# Ethernet_ACS_Toggle.net
KiCad netlist of a schematic drawn in EasyEDA Pro
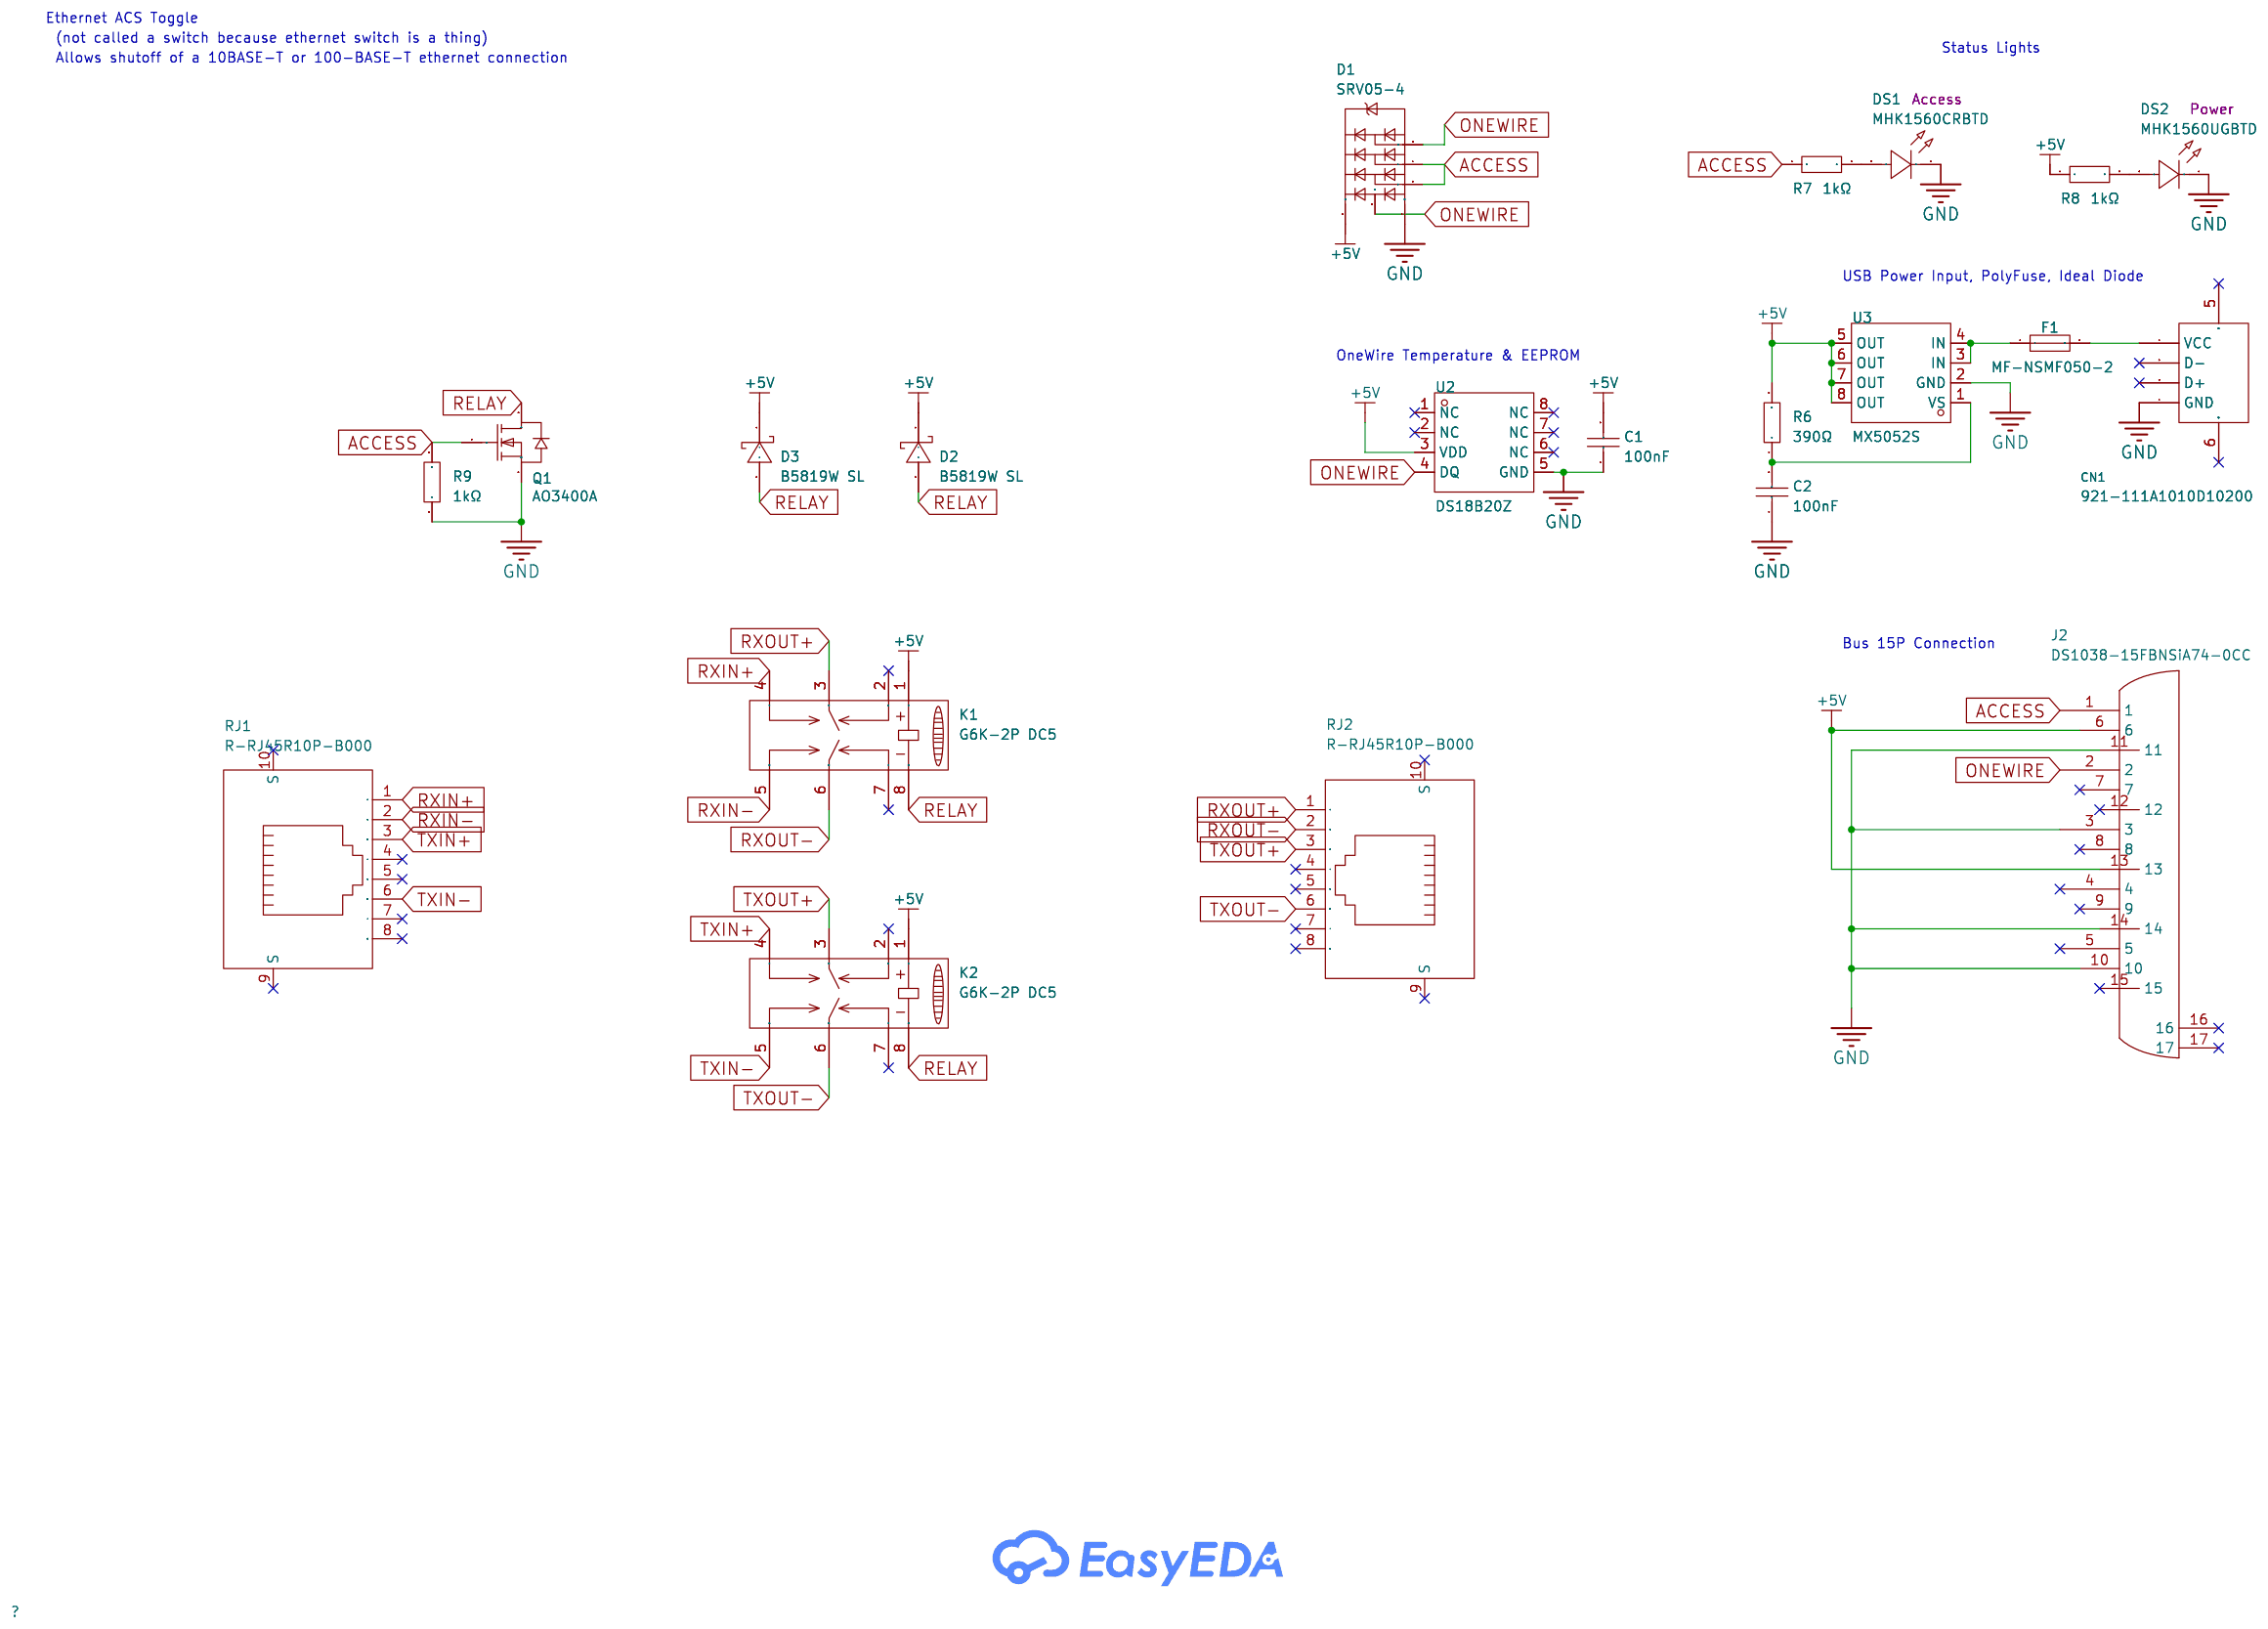
[diagram p0: schematic sheet]

(export (version "E")
  (design (tool "Eeschema 10.0.6"))
  (components
    (comp (ref "C1")
      (value "100nF")
      (footprint "easyedapro:C0805")
      (description "Capacitance:100nF Tolerance:±10% Tolerance:±10% Voltage Rating:100V Temperature Coefficient:X7R")
      (fields
        (field (name "Manufacturer Part") "CL21B104KCFNNNE")
        (field (name "Manufacturer") "SAMSUNG(三星)")
      )
      (libsource (lib "easyedapro") (part "CL21B104KCFNNNE"))
    )
    (comp (ref "C2")
      (value "100nF")
      (footprint "easyedapro:C0805")
      (description "Capacitance:100nF Tolerance:±10% Tolerance:±10% Voltage Rating:100V Temperature Coefficient:X7R")
      (fields
        (field (name "Manufacturer Part") "CL21B104KCFNNNE")
        (field (name "Manufacturer") "SAMSUNG(三星)")
      )
      (libsource (lib "easyedapro") (part "CL21B104KCFNNNE"))
    )
    (comp (ref "CN1")
      (value "921-111A1010D10200")
      (footprint "easyedapro:USB-B_TH_USB-B-FEMALE-90")
      (fields (field (name "Manufacturer") "精拓金"))
      (libsource (lib "easyedapro") (part "USB-B-Female-90"))
    )
    (comp (ref "D1")
      (value "SRV05-4")
      (footprint "easyedapro:SOT-23-6_L2.9-W1.6-P0.95-LS2.8-BL-1")
      (fields (field (name "Manufacturer") "R+O(宏嘉诚)"))
      (libsource (lib "easyedapro") (part "SRV05-4_C7420376"))
    )
    (comp (ref "D2")
      (value "B5819W SL")
      (footprint "easyedapro:SOD-123_L2.7-W1.6-LS3.7-RD-1")
      (fields (field (name "Manufacturer") "CJ(江苏长电/长晶)"))
      (libsource (lib "easyedapro") (part "B5819W_C8598"))
    )
    (comp (ref "D3")
      (value "B5819W SL")
      (footprint "easyedapro:SOD-123_L2.7-W1.6-LS3.7-RD-1")
      (fields (field (name "Manufacturer") "CJ(江苏长电/长晶)"))
      (libsource (lib "easyedapro") (part "B5819W_C8598"))
    )
    (comp (ref "DS1")
      (value "MHK1560CRBTD")
      (footprint "easyedapro:LED-TH_MHK1560UGBTD")
      (fields (field (name "Manufacturer") "MEIHUA(美华)") (field (name "Note") "Access"))
      (libsource (lib "easyedapro") (part "MHK1560CGBTD"))
    )
    (comp (ref "DS2")
      (value "MHK1560UGBTD")
      (footprint "easyedapro:LED-TH_MHK1560UGBTD")
      (fields (field (name "Manufacturer") "MEIHUA(美华)") (field (name "Note") "Power"))
      (libsource (lib "easyedapro") (part "MHK1560UGBTD"))
    )
    (comp (ref "F1")
      (value "MF-NSMF050-2")
      (footprint "easyedapro:F1206")
      (fields (field (name "Manufacturer") "BOURNS"))
      (libsource (lib "easyedapro") (part "MF-NSMF050-2"))
    )
    (comp (ref "J2")
      (value "DS1038-15FBNSiA74-0CC")
      (footprint "easyedapro:DSUB-TH_DS1038-15FBNSIA74-0CC")
      (fields (field (name "Manufacturer") "CONNFLY"))
      (libsource (lib "easyedapro") (part "DS1038-15FBNSIA74-0CC"))
    )
    (comp (ref "K1")
      (value "G6K-2P DC5")
      (footprint "easyedapro:RELAY-TH_G6K-2P")
      (fields (field (name "Manufacturer") "OMRON(欧姆龙)"))
      (libsource (lib "easyedapro") (part "G6K-2P DC5"))
    )
    (comp (ref "K2")
      (value "G6K-2P DC5")
      (footprint "easyedapro:RELAY-TH_G6K-2P")
      (fields (field (name "Manufacturer") "OMRON(欧姆龙)"))
      (libsource (lib "easyedapro") (part "G6K-2P DC5"))
    )
    (comp (ref "Q1")
      (value "AO3400A")
      (footprint "easyedapro:SOT-23-3_L2.9-W1.3-P1.90-LS2.4-BR")
      (fields (field (name "Manufacturer") "AOS"))
      (libsource (lib "easyedapro") (part "AO3400A"))
    )
    (comp (ref "R6")
      (value "390Ω")
      (footprint "easyedapro:R0805")
      (fields
        (field (name "Manufacturer Part") "0805W8F3900T5E")
        (field (name "Manufacturer") "UNI-ROYAL(厚声)")
      )
      (libsource (lib "easyedapro") (part "0805W8F3900T5E"))
    )
    (comp (ref "R7")
      (value "1kΩ")
      (footprint "easyedapro:R0805")
      (fields
        (field (name "Manufacturer Part") "0805W8F1001T5E")
        (field (name "Manufacturer") "UNI-ROYAL(厚声)")
      )
      (libsource (lib "easyedapro") (part "0805W8F1001T5E"))
    )
    (comp (ref "R8")
      (value "1kΩ")
      (footprint "easyedapro:R0805")
      (fields
        (field (name "Manufacturer Part") "0805W8F1001T5E")
        (field (name "Manufacturer") "UNI-ROYAL(厚声)")
      )
      (libsource (lib "easyedapro") (part "0805W8F1001T5E"))
    )
    (comp (ref "R9")
      (value "1kΩ")
      (footprint "easyedapro:R0805")
      (fields
        (field (name "Manufacturer Part") "0805W8F1001T5E")
        (field (name "Manufacturer") "UNI-ROYAL(厚声)")
      )
      (libsource (lib "easyedapro") (part "0805W8F1001T5E"))
    )
    (comp (ref "RJ1")
      (value "R-RJ45R10P-B000")
      (footprint "easyedapro:RJ45-TH_R-RJ45R10P-B000")
      (fields (field (name "Manufacturer") "Ckmtw(灿科盟)"))
      (libsource (lib "easyedapro") (part "R-RJ45R10P-B000"))
    )
    (comp (ref "RJ2")
      (value "R-RJ45R10P-B000")
      (footprint "easyedapro:RJ45-TH_R-RJ45R10P-B000")
      (fields (field (name "Manufacturer") "Ckmtw(灿科盟)"))
      (libsource (lib "easyedapro") (part "R-RJ45R10P-B000"))
    )
    (comp (ref "U2")
      (value "DS18B20Z")
      (footprint "easyedapro:SOP-8_L4.9-W3.9-P1.27-LS6.0-BL")
      (description "Resolution:±0.4°C Resolution:±0.4°C Supply Voltage:2.5V~5.5V Supply Voltage:2.5V~5.5V")
      (fields (field (name "Manufacturer") "UMW(友台半导体)"))
      (libsource (lib "easyedapro") (part "DS18B20Z"))
    )
    (comp (ref "U3")
      (value "MX5052S")
      (footprint "easyedapro:SOP-8_L4.9-W3.9-P1.27-LS6.0-BL")
      (fields (field (name "Manufacturer") "Wuxi Maxinmicro(无锡明芯微)"))
      (libsource (lib "easyedapro") (part "MX5052S"))
    )
  )
  (nets
    (net (code "1") (name "+5V") (class "Default")
      (node (ref "C1") (pin "2") (pinfunction "2_2") (pintype "input"))
      (node (ref "D1") (pin "5") (pinfunction "5_5") (pintype "unspecified"))
      (node (ref "D2") (pin "1") (pinfunction "-_1") (pintype "unspecified"))
      (node (ref "D3") (pin "1") (pinfunction "-_1") (pintype "unspecified"))
      (node (ref "J2") (pin "13") (pinfunction "13_13") (pintype "unspecified"))
      (node (ref "J2") (pin "6") (pinfunction "6_6") (pintype "unspecified"))
      (node (ref "K1") (pin "1") (pinfunction "1_1") (pintype "unspecified"))
      (node (ref "K2") (pin "1") (pinfunction "1_1") (pintype "unspecified"))
      (node (ref "R6") (pin "2") (pinfunction "2_2") (pintype "input"))
      (node (ref "R8") (pin "1") (pinfunction "1_1") (pintype "input"))
      (node (ref "U2") (pin "3") (pinfunction "VDD_3") (pintype "unspecified"))
      (node (ref "U3") (pin "5") (pinfunction "OUT_5") (pintype "unspecified"))
      (node (ref "U3") (pin "6") (pinfunction "OUT_6") (pintype "unspecified"))
      (node (ref "U3") (pin "7") (pinfunction "OUT_7") (pintype "unspecified"))
      (node (ref "U3") (pin "8") (pinfunction "OUT_8") (pintype "unspecified"))
    )
    (net (code "2") (name "ACCESS") (class "Default")
      (node (ref "D1") (pin "3") (pinfunction "3_3") (pintype "unspecified"))
      (node (ref "D1") (pin "4") (pinfunction "4_4") (pintype "unspecified"))
      (node (ref "J2") (pin "1") (pinfunction "1_1") (pintype "unspecified"))
      (node (ref "Q1") (pin "1") (pinfunction "G_1") (pintype "unspecified"))
      (node (ref "R7") (pin "1") (pinfunction "1_1") (pintype "input"))
      (node (ref "R9") (pin "2") (pinfunction "2_2") (pintype "input"))
    )
    (net (code "3") (name "GND") (class "Default")
      (node (ref "C1") (pin "1") (pinfunction "1_1") (pintype "input"))
      (node (ref "C2") (pin "1") (pinfunction "1_1") (pintype "input"))
      (node (ref "CN1") (pin "4") (pinfunction "GND_4") (pintype "input"))
      (node (ref "D1") (pin "2") (pinfunction "2_2") (pintype "unspecified"))
      (node (ref "DS1") (pin "1") (pinfunction "K_1") (pintype "unspecified"))
      (node (ref "DS2") (pin "1") (pinfunction "K_1") (pintype "unspecified"))
      (node (ref "J2") (pin "10") (pinfunction "10_10") (pintype "unspecified"))
      (node (ref "J2") (pin "11") (pinfunction "11_11") (pintype "unspecified"))
      (node (ref "J2") (pin "14") (pinfunction "14_14") (pintype "unspecified"))
      (node (ref "J2") (pin "3") (pinfunction "3_3") (pintype "unspecified"))
      (node (ref "Q1") (pin "2") (pinfunction "S_2") (pintype "unspecified"))
      (node (ref "R9") (pin "1") (pinfunction "1_1") (pintype "input"))
      (node (ref "U2") (pin "5") (pinfunction "GND_5") (pintype "unspecified"))
      (node (ref "U3") (pin "2") (pinfunction "GND_2") (pintype "unspecified"))
    )
    (net (code "4") (name "Net-(CN1-VCC)") (class "Default")
      (node (ref "CN1") (pin "1") (pinfunction "VCC_1") (pintype "input"))
      (node (ref "F1") (pin "2") (pinfunction "2_2") (pintype "unspecified"))
    )
    (net (code "5") (name "Net-(DS1-A)") (class "Default")
      (node (ref "DS1") (pin "2") (pinfunction "A_2") (pintype "unspecified"))
      (node (ref "R7") (pin "2") (pinfunction "2_2") (pintype "input"))
    )
    (net (code "6") (name "Net-(DS2-A)") (class "Default")
      (node (ref "DS2") (pin "2") (pinfunction "A_2") (pintype "unspecified"))
      (node (ref "R8") (pin "2") (pinfunction "2_2") (pintype "input"))
    )
    (net (code "7") (name "Net-(F1-Pad1)") (class "Default")
      (node (ref "F1") (pin "1") (pinfunction "1_1") (pintype "unspecified"))
      (node (ref "U3") (pin "3") (pinfunction "IN_3") (pintype "unspecified"))
      (node (ref "U3") (pin "4") (pinfunction "IN_4") (pintype "unspecified"))
    )
    (net (code "8") (name "Net-(U3-VS)") (class "Default")
      (node (ref "C2") (pin "2") (pinfunction "2_2") (pintype "input"))
      (node (ref "R6") (pin "1") (pinfunction "1_1") (pintype "input"))
      (node (ref "U3") (pin "1") (pinfunction "VS_1") (pintype "unspecified"))
    )
    (net (code "9") (name "ONEWIRE") (class "Default")
      (node (ref "D1") (pin "1") (pinfunction "1_1") (pintype "unspecified"))
      (node (ref "D1") (pin "6") (pinfunction "6_6") (pintype "unspecified"))
      (node (ref "J2") (pin "2") (pinfunction "2_2") (pintype "unspecified"))
      (node (ref "U2") (pin "4") (pinfunction "DQ_4") (pintype "unspecified"))
    )
    (net (code "10") (name "RELAY") (class "Default")
      (node (ref "D2") (pin "2") (pinfunction "+_2") (pintype "unspecified"))
      (node (ref "D3") (pin "2") (pinfunction "+_2") (pintype "unspecified"))
      (node (ref "K1") (pin "8") (pinfunction "8_8") (pintype "unspecified"))
      (node (ref "K2") (pin "8") (pinfunction "8_8") (pintype "unspecified"))
      (node (ref "Q1") (pin "3") (pinfunction "D_3") (pintype "unspecified"))
    )
    (net (code "11") (name "RXIN+") (class "Default")
      (node (ref "K1") (pin "4") (pinfunction "4_4") (pintype "unspecified"))
      (node (ref "RJ1") (pin "1") (pinfunction "1_1") (pintype "unspecified"))
    )
    (net (code "12") (name "RXIN-") (class "Default")
      (node (ref "K1") (pin "5") (pinfunction "5_5") (pintype "unspecified"))
      (node (ref "RJ1") (pin "2") (pinfunction "2_2") (pintype "unspecified"))
    )
    (net (code "13") (name "RXOUT+") (class "Default")
      (node (ref "K1") (pin "3") (pinfunction "3_3") (pintype "unspecified"))
      (node (ref "RJ2") (pin "1") (pinfunction "1_1") (pintype "unspecified"))
    )
    (net (code "14") (name "RXOUT-") (class "Default")
      (node (ref "K1") (pin "6") (pinfunction "6_6") (pintype "unspecified"))
      (node (ref "RJ2") (pin "2") (pinfunction "2_2") (pintype "unspecified"))
    )
    (net (code "15") (name "TXIN+") (class "Default")
      (node (ref "K2") (pin "4") (pinfunction "4_4") (pintype "unspecified"))
      (node (ref "RJ1") (pin "3") (pinfunction "3_3") (pintype "unspecified"))
    )
    (net (code "16") (name "TXIN-") (class "Default")
      (node (ref "K2") (pin "5") (pinfunction "5_5") (pintype "unspecified"))
      (node (ref "RJ1") (pin "6") (pinfunction "6_6") (pintype "unspecified"))
    )
    (net (code "17") (name "TXOUT+") (class "Default")
      (node (ref "K2") (pin "3") (pinfunction "3_3") (pintype "unspecified"))
      (node (ref "RJ2") (pin "3") (pinfunction "3_3") (pintype "unspecified"))
    )
    (net (code "18") (name "TXOUT-") (class "Default")
      (node (ref "K2") (pin "6") (pinfunction "6_6") (pintype "unspecified"))
      (node (ref "RJ2") (pin "6") (pinfunction "6_6") (pintype "unspecified"))
    )
    (net (code "19") (name "unconnected-(CN1-D+-Pad3)") (class "Default")
      (node (ref "CN1") (pin "3") (pinfunction "D+_3") (pintype "input+no_connect"))
    )
    (net (code "20") (name "unconnected-(CN1-D--Pad2)") (class "Default")
      (node (ref "CN1") (pin "2") (pinfunction "D-_2") (pintype "input+no_connect"))
    )
    (net (code "21") (name "unconnected-(CN1-SH1-Pad5)") (class "Default")
      (node (ref "CN1") (pin "5") (pinfunction "SH1_5") (pintype "input+no_connect"))
    )
    (net (code "22") (name "unconnected-(CN1-SH2-Pad6)") (class "Default")
      (node (ref "CN1") (pin "6") (pinfunction "SH2_6") (pintype "input+no_connect"))
    )
    (net (code "23") (name "unconnected-(J2-Pad4)") (class "Default")
      (node (ref "J2") (pin "4") (pinfunction "4_4") (pintype "unspecified+no_connect"))
    )
    (net (code "24") (name "unconnected-(J2-Pad5)") (class "Default")
      (node (ref "J2") (pin "5") (pinfunction "5_5") (pintype "unspecified+no_connect"))
    )
    (net (code "25") (name "unconnected-(J2-Pad7)") (class "Default")
      (node (ref "J2") (pin "7") (pinfunction "7_7") (pintype "unspecified+no_connect"))
    )
    (net (code "26") (name "unconnected-(J2-Pad8)") (class "Default")
      (node (ref "J2") (pin "8") (pinfunction "8_8") (pintype "unspecified+no_connect"))
    )
    (net (code "27") (name "unconnected-(J2-Pad9)") (class "Default")
      (node (ref "J2") (pin "9") (pinfunction "9_9") (pintype "unspecified+no_connect"))
    )
    (net (code "28") (name "unconnected-(J2-Pad12)") (class "Default")
      (node (ref "J2") (pin "12") (pinfunction "12_12") (pintype "unspecified+no_connect"))
    )
    (net (code "29") (name "unconnected-(J2-Pad15)") (class "Default")
      (node (ref "J2") (pin "15") (pinfunction "15_15") (pintype "unspecified+no_connect"))
    )
    (net (code "30") (name "unconnected-(J2-Pad16)") (class "Default")
      (node (ref "J2") (pin "16") (pinfunction "16_16") (pintype "unspecified+no_connect"))
    )
    (net (code "31") (name "unconnected-(J2-Pad17)") (class "Default")
      (node (ref "J2") (pin "17") (pinfunction "17_17") (pintype "unspecified+no_connect"))
    )
    (net (code "32") (name "unconnected-(K1-Pad2)") (class "Default")
      (node (ref "K1") (pin "2") (pinfunction "2_2") (pintype "unspecified+no_connect"))
    )
    (net (code "33") (name "unconnected-(K1-Pad7)") (class "Default")
      (node (ref "K1") (pin "7") (pinfunction "7_7") (pintype "unspecified+no_connect"))
    )
    (net (code "34") (name "unconnected-(K2-Pad2)") (class "Default")
      (node (ref "K2") (pin "2") (pinfunction "2_2") (pintype "unspecified+no_connect"))
    )
    (net (code "35") (name "unconnected-(K2-Pad7)") (class "Default")
      (node (ref "K2") (pin "7") (pinfunction "7_7") (pintype "unspecified+no_connect"))
    )
    (net (code "36") (name "unconnected-(RJ1-Pad4)") (class "Default")
      (node (ref "RJ1") (pin "4") (pinfunction "4_4") (pintype "unspecified+no_connect"))
    )
    (net (code "37") (name "unconnected-(RJ1-Pad5)") (class "Default")
      (node (ref "RJ1") (pin "5") (pinfunction "5_5") (pintype "unspecified+no_connect"))
    )
    (net (code "38") (name "unconnected-(RJ1-Pad7)") (class "Default")
      (node (ref "RJ1") (pin "7") (pinfunction "7_7") (pintype "unspecified+no_connect"))
    )
    (net (code "39") (name "unconnected-(RJ1-Pad8)") (class "Default")
      (node (ref "RJ1") (pin "8") (pinfunction "8_8") (pintype "unspecified+no_connect"))
    )
    (net (code "40") (name "unconnected-(RJ1-S-Pad9)") (class "Default")
      (node (ref "RJ1") (pin "9") (pinfunction "S_9") (pintype "unspecified+no_connect"))
    )
    (net (code "41") (name "unconnected-(RJ1-S-Pad10)") (class "Default")
      (node (ref "RJ1") (pin "10") (pinfunction "S_10") (pintype "unspecified+no_connect"))
    )
    (net (code "42") (name "unconnected-(RJ2-Pad4)") (class "Default")
      (node (ref "RJ2") (pin "4") (pinfunction "4_4") (pintype "unspecified+no_connect"))
    )
    (net (code "43") (name "unconnected-(RJ2-Pad5)") (class "Default")
      (node (ref "RJ2") (pin "5") (pinfunction "5_5") (pintype "unspecified+no_connect"))
    )
    (net (code "44") (name "unconnected-(RJ2-Pad7)") (class "Default")
      (node (ref "RJ2") (pin "7") (pinfunction "7_7") (pintype "unspecified+no_connect"))
    )
    (net (code "45") (name "unconnected-(RJ2-Pad8)") (class "Default")
      (node (ref "RJ2") (pin "8") (pinfunction "8_8") (pintype "unspecified+no_connect"))
    )
    (net (code "46") (name "unconnected-(RJ2-S-Pad9)") (class "Default")
      (node (ref "RJ2") (pin "9") (pinfunction "S_9") (pintype "unspecified+no_connect"))
    )
    (net (code "47") (name "unconnected-(RJ2-S-Pad10)") (class "Default")
      (node (ref "RJ2") (pin "10") (pinfunction "S_10") (pintype "unspecified+no_connect"))
    )
    (net (code "48") (name "unconnected-(U2-NC-Pad1)") (class "Default")
      (node (ref "U2") (pin "1") (pinfunction "NC_1") (pintype "unspecified+no_connect"))
    )
    (net (code "49") (name "unconnected-(U2-NC-Pad2)") (class "Default")
      (node (ref "U2") (pin "2") (pinfunction "NC_2") (pintype "unspecified+no_connect"))
    )
    (net (code "50") (name "unconnected-(U2-NC-Pad6)") (class "Default")
      (node (ref "U2") (pin "6") (pinfunction "NC_6") (pintype "unspecified+no_connect"))
    )
    (net (code "51") (name "unconnected-(U2-NC-Pad7)") (class "Default")
      (node (ref "U2") (pin "7") (pinfunction "NC_7") (pintype "unspecified+no_connect"))
    )
    (net (code "52") (name "unconnected-(U2-NC-Pad8)") (class "Default")
      (node (ref "U2") (pin "8") (pinfunction "NC_8") (pintype "unspecified+no_connect"))
    )
  )
)
